# DM542T.net
KiCad netlist of a schematic drawn in EAGLE
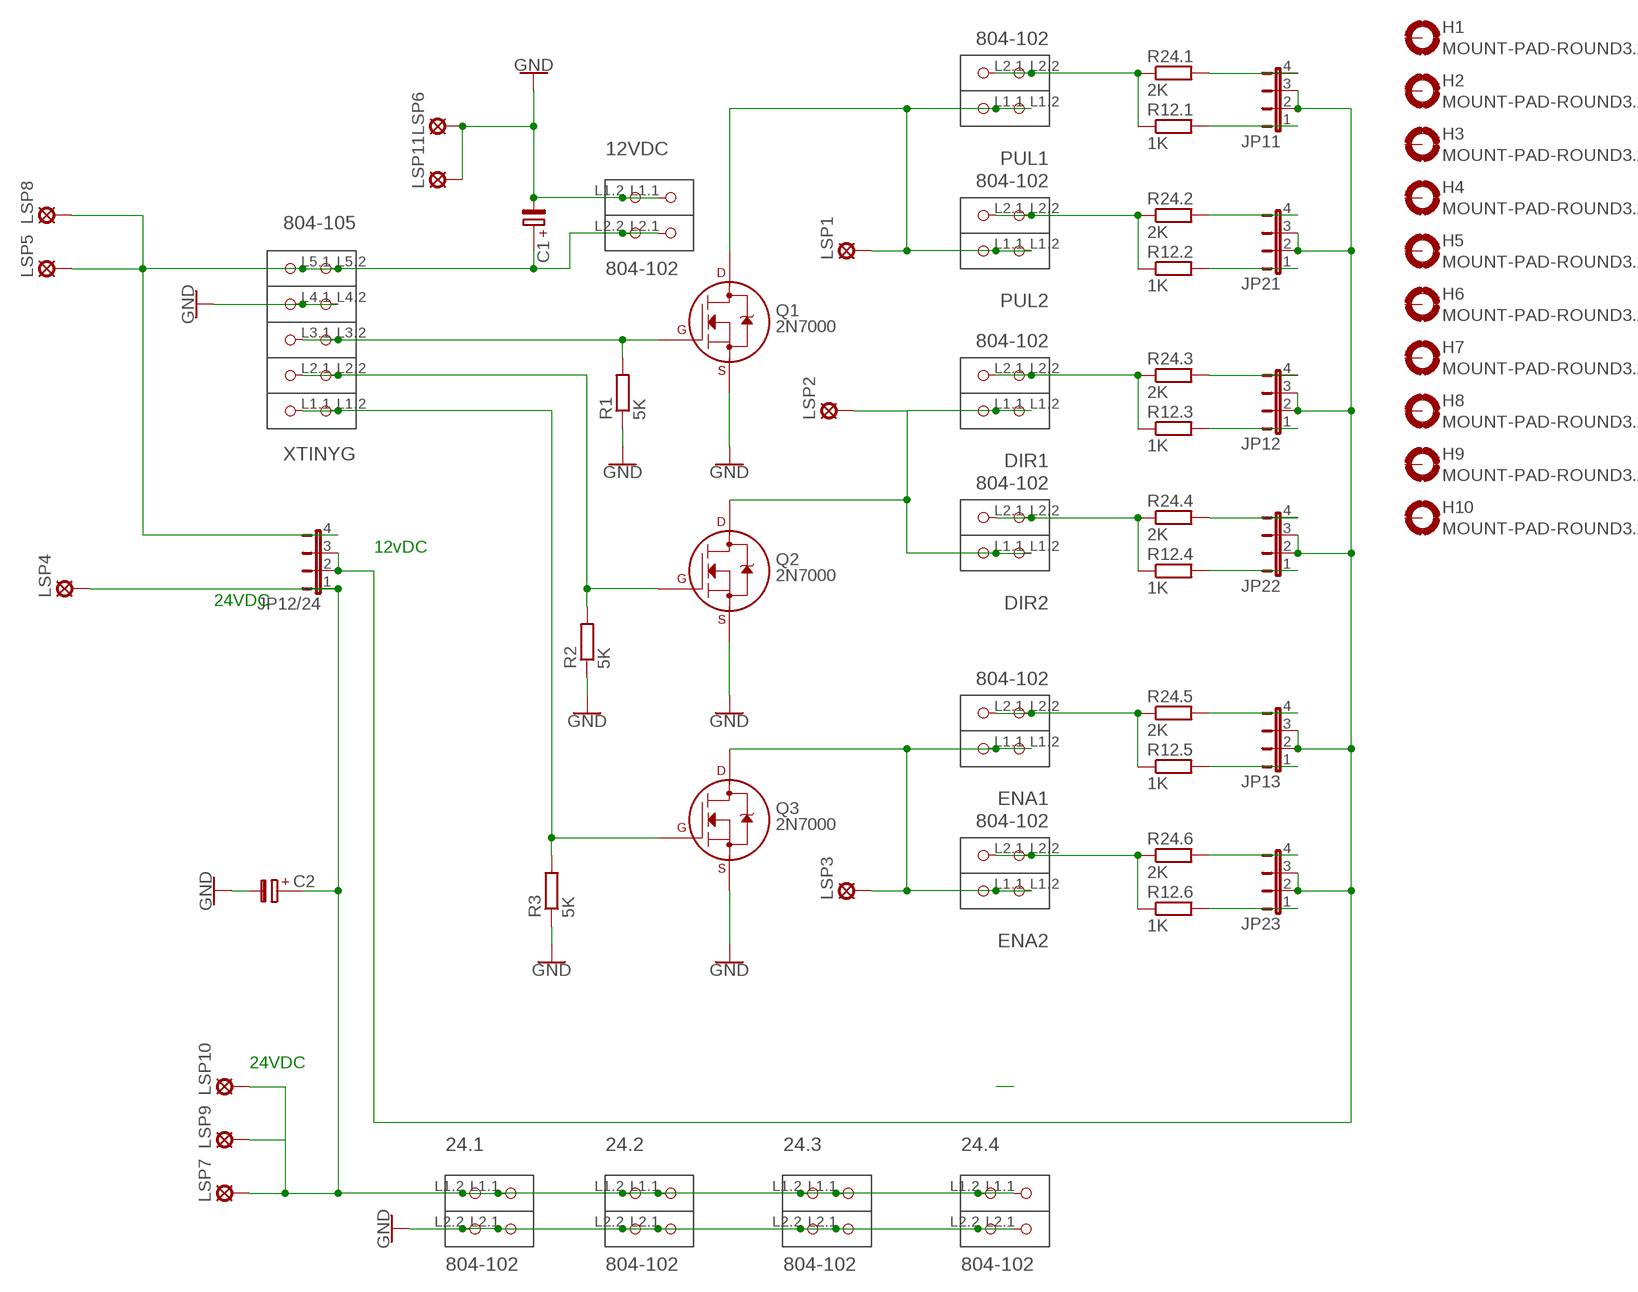
[diagram p0: schematic, sheet 1]

(export (version "E")
  (design (tool "Eeschema 10.0.6"))
  (components
    (comp (ref "12VDC")
      (value "804-102")
      (footprint "eagle-import:P-804-102")
      (libsource (lib "eagle-import") (part "804-102"))
    )
    (comp (ref "24.1")
      (value "804-102")
      (footprint "eagle-import:P-804-102")
      (libsource (lib "eagle-import") (part "804-102"))
    )
    (comp (ref "24.2")
      (value "804-102")
      (footprint "eagle-import:P-804-102")
      (libsource (lib "eagle-import") (part "804-102"))
    )
    (comp (ref "24.3")
      (value "804-102")
      (footprint "eagle-import:P-804-102")
      (libsource (lib "eagle-import") (part "804-102"))
    )
    (comp (ref "24.4")
      (value "804-102")
      (footprint "eagle-import:P-804-102")
      (libsource (lib "eagle-import") (part "804-102"))
    )
    (comp (ref "C1")
      (value "C-PR-3,5X10")
      (footprint "eagle-import:E3,5-10")
      (libsource (lib "eagle-import") (part "C-PR-3,5X10"))
    )
    (comp (ref "C2")
      (value "C-PR-3,5X10")
      (footprint "eagle-import:E3,5-10")
      (libsource (lib "eagle-import") (part "C-PR-3,5X10"))
    )
    (comp (ref "DIR1")
      (value "804-102")
      (footprint "eagle-import:P-804-102")
      (libsource (lib "eagle-import") (part "804-102"))
    )
    (comp (ref "DIR2")
      (value "804-102")
      (footprint "eagle-import:P-804-102")
      (libsource (lib "eagle-import") (part "804-102"))
    )
    (comp (ref "ENA1")
      (value "804-102")
      (footprint "eagle-import:P-804-102")
      (libsource (lib "eagle-import") (part "804-102"))
    )
    (comp (ref "ENA2")
      (value "804-102")
      (footprint "eagle-import:P-804-102")
      (libsource (lib "eagle-import") (part "804-102"))
    )
    (comp (ref "H1")
      (value "MOUNT-PAD-ROUND3.2")
      (footprint "eagle-import:3,2-PAD")
      (libsource (lib "eagle-import") (part "MOUNT-PAD-ROUND3.2"))
    )
    (comp (ref "H2")
      (value "MOUNT-PAD-ROUND3.2")
      (footprint "eagle-import:3,2-PAD")
      (libsource (lib "eagle-import") (part "MOUNT-PAD-ROUND3.2"))
    )
    (comp (ref "H3")
      (value "MOUNT-PAD-ROUND3.2")
      (footprint "eagle-import:3,2-PAD")
      (libsource (lib "eagle-import") (part "MOUNT-PAD-ROUND3.2"))
    )
    (comp (ref "H4")
      (value "MOUNT-PAD-ROUND3.2")
      (footprint "eagle-import:3,2-PAD")
      (libsource (lib "eagle-import") (part "MOUNT-PAD-ROUND3.2"))
    )
    (comp (ref "H5")
      (value "MOUNT-PAD-ROUND3.2")
      (footprint "eagle-import:3,2-PAD")
      (libsource (lib "eagle-import") (part "MOUNT-PAD-ROUND3.2"))
    )
    (comp (ref "H6")
      (value "MOUNT-PAD-ROUND3.2")
      (footprint "eagle-import:3,2-PAD")
      (libsource (lib "eagle-import") (part "MOUNT-PAD-ROUND3.2"))
    )
    (comp (ref "H7")
      (value "MOUNT-PAD-ROUND3.2")
      (footprint "eagle-import:3,2-PAD")
      (libsource (lib "eagle-import") (part "MOUNT-PAD-ROUND3.2"))
    )
    (comp (ref "H8")
      (value "MOUNT-PAD-ROUND3.2")
      (footprint "eagle-import:3,2-PAD")
      (libsource (lib "eagle-import") (part "MOUNT-PAD-ROUND3.2"))
    )
    (comp (ref "H9")
      (value "MOUNT-PAD-ROUND3.2")
      (footprint "eagle-import:3,2-PAD")
      (libsource (lib "eagle-import") (part "MOUNT-PAD-ROUND3.2"))
    )
    (comp (ref "H10")
      (value "MOUNT-PAD-ROUND3.2")
      (footprint "eagle-import:3,2-PAD")
      (libsource (lib "eagle-import") (part "MOUNT-PAD-ROUND3.2"))
    )
    (comp (ref "JP11")
      (value "JP4E")
      (footprint "eagle-import:JP4")
      (libsource (lib "eagle-import") (part "JP4E"))
    )
    (comp (ref "JP12")
      (value "JP4E")
      (footprint "eagle-import:JP4")
      (libsource (lib "eagle-import") (part "JP4E"))
    )
    (comp (ref "JP12/24")
      (value "JP4E")
      (footprint "eagle-import:JP4")
      (libsource (lib "eagle-import") (part "JP4E"))
    )
    (comp (ref "JP13")
      (value "JP4E")
      (footprint "eagle-import:JP4")
      (libsource (lib "eagle-import") (part "JP4E"))
    )
    (comp (ref "JP21")
      (value "JP4E")
      (footprint "eagle-import:JP4")
      (libsource (lib "eagle-import") (part "JP4E"))
    )
    (comp (ref "JP22")
      (value "JP4E")
      (footprint "eagle-import:JP4")
      (libsource (lib "eagle-import") (part "JP4E"))
    )
    (comp (ref "JP23")
      (value "JP4E")
      (footprint "eagle-import:JP4")
      (libsource (lib "eagle-import") (part "JP4E"))
    )
    (comp (ref "LSP1")
      (value "LSP10")
      (footprint "eagle-import:LSP10")
      (libsource (lib "eagle-import") (part "LSP10"))
    )
    (comp (ref "LSP2")
      (value "LSP10")
      (footprint "eagle-import:LSP10")
      (libsource (lib "eagle-import") (part "LSP10"))
    )
    (comp (ref "LSP3")
      (value "LSP10")
      (footprint "eagle-import:LSP10")
      (libsource (lib "eagle-import") (part "LSP10"))
    )
    (comp (ref "LSP4")
      (value "LSP10")
      (footprint "eagle-import:LSP10")
      (libsource (lib "eagle-import") (part "LSP10"))
    )
    (comp (ref "LSP5")
      (value "LSP10")
      (footprint "eagle-import:LSP10")
      (libsource (lib "eagle-import") (part "LSP10"))
    )
    (comp (ref "LSP6")
      (value "LSP10")
      (footprint "eagle-import:LSP10")
      (libsource (lib "eagle-import") (part "LSP10"))
    )
    (comp (ref "LSP7")
      (value "LSP10")
      (footprint "eagle-import:LSP10")
      (libsource (lib "eagle-import") (part "LSP10"))
    )
    (comp (ref "LSP8")
      (value "LSP10")
      (footprint "eagle-import:LSP10")
      (libsource (lib "eagle-import") (part "LSP10"))
    )
    (comp (ref "LSP9")
      (value "LSP10")
      (footprint "eagle-import:LSP10")
      (libsource (lib "eagle-import") (part "LSP10"))
    )
    (comp (ref "LSP10")
      (value "LSP10")
      (footprint "eagle-import:LSP10")
      (libsource (lib "eagle-import") (part "LSP10"))
    )
    (comp (ref "LSP11")
      (value "LSP10")
      (footprint "eagle-import:LSP10")
      (libsource (lib "eagle-import") (part "LSP10"))
    )
    (comp (ref "PUL1")
      (value "804-102")
      (footprint "eagle-import:P-804-102")
      (libsource (lib "eagle-import") (part "804-102"))
    )
    (comp (ref "PUL2")
      (value "804-102")
      (footprint "eagle-import:P-804-102")
      (libsource (lib "eagle-import") (part "804-102"))
    )
    (comp (ref "Q1")
      (value "2N7000")
      (footprint "eagle-import:TO-92")
      (libsource (lib "eagle-import") (part "2N700_TO920"))
    )
    (comp (ref "Q2")
      (value "2N7000")
      (footprint "eagle-import:TO-92")
      (libsource (lib "eagle-import") (part "2N700_TO920"))
    )
    (comp (ref "Q3")
      (value "2N7000")
      (footprint "eagle-import:TO-92")
      (libsource (lib "eagle-import") (part "2N700_TO920"))
    )
    (comp (ref "R1")
      (value "5K")
      (footprint "eagle-import:0207_15")
      (libsource (lib "eagle-import") (part "R-EU_0207/15"))
    )
    (comp (ref "R2")
      (value "5K")
      (footprint "eagle-import:0207_15")
      (libsource (lib "eagle-import") (part "R-EU_0207/15"))
    )
    (comp (ref "R3")
      (value "5K")
      (footprint "eagle-import:0207_15")
      (libsource (lib "eagle-import") (part "R-EU_0207/15"))
    )
    (comp (ref "R12.1")
      (value "1K")
      (footprint "eagle-import:0207_15")
      (libsource (lib "eagle-import") (part "R-EU_0207/15"))
    )
    (comp (ref "R12.2")
      (value "1K")
      (footprint "eagle-import:0207_15")
      (libsource (lib "eagle-import") (part "R-EU_0207/15"))
    )
    (comp (ref "R12.3")
      (value "1K")
      (footprint "eagle-import:0207_15")
      (libsource (lib "eagle-import") (part "R-EU_0207/15"))
    )
    (comp (ref "R12.4")
      (value "1K")
      (footprint "eagle-import:0207_15")
      (libsource (lib "eagle-import") (part "R-EU_0207/15"))
    )
    (comp (ref "R12.5")
      (value "1K")
      (footprint "eagle-import:0207_15")
      (libsource (lib "eagle-import") (part "R-EU_0207/15"))
    )
    (comp (ref "R12.6")
      (value "1K")
      (footprint "eagle-import:0207_15")
      (libsource (lib "eagle-import") (part "R-EU_0207/15"))
    )
    (comp (ref "R24.1")
      (value "2K")
      (footprint "eagle-import:0207_15")
      (libsource (lib "eagle-import") (part "R-EU_0207/15"))
    )
    (comp (ref "R24.2")
      (value "2K")
      (footprint "eagle-import:0207_15")
      (libsource (lib "eagle-import") (part "R-EU_0207/15"))
    )
    (comp (ref "R24.3")
      (value "2K")
      (footprint "eagle-import:0207_15")
      (libsource (lib "eagle-import") (part "R-EU_0207/15"))
    )
    (comp (ref "R24.4")
      (value "2K")
      (footprint "eagle-import:0207_15")
      (libsource (lib "eagle-import") (part "R-EU_0207/15"))
    )
    (comp (ref "R24.5")
      (value "2K")
      (footprint "eagle-import:0207_15")
      (libsource (lib "eagle-import") (part "R-EU_0207/15"))
    )
    (comp (ref "R24.6")
      (value "2K")
      (footprint "eagle-import:0207_15")
      (libsource (lib "eagle-import") (part "R-EU_0207/15"))
    )
    (comp (ref "XTINYG")
      (value "804-105")
      (footprint "eagle-import:P-804-105")
      (libsource (lib "eagle-import") (part "804-105"))
    )
  )
  (nets
    (net (code "1") (name "GND") (class "Default")
      (node (ref "12VDC") (pin "L1.1") (pinfunction "P1.1_L1.1") (pintype "bidirectional"))
      (node (ref "12VDC") (pin "L1.2") (pinfunction "P1.2_L1.2") (pintype "bidirectional"))
      (node (ref "24.1") (pin "L2.1") (pinfunction "P2.1_L2.1") (pintype "bidirectional"))
      (node (ref "24.1") (pin "L2.2") (pinfunction "P2.2_L2.2") (pintype "bidirectional"))
      (node (ref "24.2") (pin "L2.1") (pinfunction "P2.1_L2.1") (pintype "bidirectional"))
      (node (ref "24.2") (pin "L2.2") (pinfunction "P2.2_L2.2") (pintype "bidirectional"))
      (node (ref "24.3") (pin "L2.1") (pinfunction "P2.1_L2.1") (pintype "bidirectional"))
      (node (ref "24.3") (pin "L2.2") (pinfunction "P2.2_L2.2") (pintype "bidirectional"))
      (node (ref "24.4") (pin "L2.1") (pinfunction "P2.1_L2.1") (pintype "bidirectional"))
      (node (ref "24.4") (pin "L2.2") (pinfunction "P2.2_L2.2") (pintype "bidirectional"))
      (node (ref "C1") (pin "-") (pinfunction "-_-") (pintype "passive"))
      (node (ref "C2") (pin "-") (pinfunction "-_-") (pintype "passive"))
      (node (ref "LSP11") (pin "MP") (pinfunction "MP_MP") (pintype "passive"))
      (node (ref "LSP6") (pin "MP") (pinfunction "MP_MP") (pintype "passive"))
      (node (ref "Q1") (pin "1") (pinfunction "S_1") (pintype "bidirectional"))
      (node (ref "Q2") (pin "1") (pinfunction "S_1") (pintype "bidirectional"))
      (node (ref "Q3") (pin "1") (pinfunction "S_1") (pintype "bidirectional"))
      (node (ref "R1") (pin "1") (pinfunction "1_1") (pintype "passive"))
      (node (ref "R2") (pin "1") (pinfunction "1_1") (pintype "passive"))
      (node (ref "R3") (pin "1") (pinfunction "1_1") (pintype "passive"))
      (node (ref "XTINYG") (pin "L4.1") (pinfunction "P4.1_L4.1") (pintype "bidirectional"))
      (node (ref "XTINYG") (pin "L4.2") (pinfunction "P4.2_L4.2") (pintype "bidirectional"))
    )
    (net (code "2") (name "Net-(12VDC-P2.1)") (class "Default")
      (node (ref "12VDC") (pin "L2.1") (pinfunction "P2.1_L2.1") (pintype "bidirectional"))
      (node (ref "12VDC") (pin "L2.2") (pinfunction "P2.2_L2.2") (pintype "bidirectional"))
      (node (ref "C1") (pin "+") (pinfunction "+_+") (pintype "passive"))
      (node (ref "JP12/24") (pin "4") (pinfunction "4_4") (pintype "passive"))
      (node (ref "LSP5") (pin "MP") (pinfunction "MP_MP") (pintype "passive"))
      (node (ref "LSP8") (pin "MP") (pinfunction "MP_MP") (pintype "passive"))
      (node (ref "XTINYG") (pin "L5.1") (pinfunction "P5.1_L5.1") (pintype "bidirectional"))
      (node (ref "XTINYG") (pin "L5.2") (pinfunction "P5.2_L5.2") (pintype "bidirectional"))
    )
    (net (code "3") (name "Net-(24.1-P1.1)") (class "Default")
      (node (ref "24.1") (pin "L1.1") (pinfunction "P1.1_L1.1") (pintype "bidirectional"))
      (node (ref "24.1") (pin "L1.2") (pinfunction "P1.2_L1.2") (pintype "bidirectional"))
      (node (ref "24.2") (pin "L1.1") (pinfunction "P1.1_L1.1") (pintype "bidirectional"))
      (node (ref "24.2") (pin "L1.2") (pinfunction "P1.2_L1.2") (pintype "bidirectional"))
      (node (ref "24.3") (pin "L1.1") (pinfunction "P1.1_L1.1") (pintype "bidirectional"))
      (node (ref "24.3") (pin "L1.2") (pinfunction "P1.2_L1.2") (pintype "bidirectional"))
      (node (ref "24.4") (pin "L1.1") (pinfunction "P1.1_L1.1") (pintype "bidirectional"))
      (node (ref "24.4") (pin "L1.2") (pinfunction "P1.2_L1.2") (pintype "bidirectional"))
      (node (ref "C2") (pin "+") (pinfunction "+_+") (pintype "passive"))
      (node (ref "JP12/24") (pin "1") (pinfunction "1_1") (pintype "passive"))
      (node (ref "LSP10") (pin "MP") (pinfunction "MP_MP") (pintype "passive"))
      (node (ref "LSP4") (pin "MP") (pinfunction "MP_MP") (pintype "passive"))
      (node (ref "LSP7") (pin "MP") (pinfunction "MP_MP") (pintype "passive"))
      (node (ref "LSP9") (pin "MP") (pinfunction "MP_MP") (pintype "passive"))
    )
    (net (code "4") (name "Net-(DIR1-P1.1)") (class "Default")
      (node (ref "DIR1") (pin "L1.1") (pinfunction "P1.1_L1.1") (pintype "bidirectional"))
      (node (ref "DIR1") (pin "L1.2") (pinfunction "P1.2_L1.2") (pintype "bidirectional"))
      (node (ref "DIR2") (pin "L1.1") (pinfunction "P1.1_L1.1") (pintype "bidirectional"))
      (node (ref "DIR2") (pin "L1.2") (pinfunction "P1.2_L1.2") (pintype "bidirectional"))
      (node (ref "LSP2") (pin "MP") (pinfunction "MP_MP") (pintype "passive"))
      (node (ref "Q2") (pin "3") (pinfunction "D_3") (pintype "bidirectional"))
    )
    (net (code "5") (name "Net-(DIR1-P2.1)") (class "Default")
      (node (ref "DIR1") (pin "L2.1") (pinfunction "P2.1_L2.1") (pintype "bidirectional"))
      (node (ref "DIR1") (pin "L2.2") (pinfunction "P2.2_L2.2") (pintype "bidirectional"))
      (node (ref "R12.3") (pin "1") (pinfunction "1_1") (pintype "passive"))
      (node (ref "R24.3") (pin "1") (pinfunction "1_1") (pintype "passive"))
    )
    (net (code "6") (name "Net-(DIR2-P2.1)") (class "Default")
      (node (ref "DIR2") (pin "L2.1") (pinfunction "P2.1_L2.1") (pintype "bidirectional"))
      (node (ref "DIR2") (pin "L2.2") (pinfunction "P2.2_L2.2") (pintype "bidirectional"))
      (node (ref "R12.4") (pin "1") (pinfunction "1_1") (pintype "passive"))
      (node (ref "R24.4") (pin "1") (pinfunction "1_1") (pintype "passive"))
    )
    (net (code "7") (name "Net-(ENA1-P1.1)") (class "Default")
      (node (ref "ENA1") (pin "L1.1") (pinfunction "P1.1_L1.1") (pintype "bidirectional"))
      (node (ref "ENA1") (pin "L1.2") (pinfunction "P1.2_L1.2") (pintype "bidirectional"))
      (node (ref "ENA2") (pin "L1.1") (pinfunction "P1.1_L1.1") (pintype "bidirectional"))
      (node (ref "ENA2") (pin "L1.2") (pinfunction "P1.2_L1.2") (pintype "bidirectional"))
      (node (ref "LSP3") (pin "MP") (pinfunction "MP_MP") (pintype "passive"))
      (node (ref "Q3") (pin "3") (pinfunction "D_3") (pintype "bidirectional"))
    )
    (net (code "8") (name "Net-(ENA1-P2.1)") (class "Default")
      (node (ref "ENA1") (pin "L2.1") (pinfunction "P2.1_L2.1") (pintype "bidirectional"))
      (node (ref "ENA1") (pin "L2.2") (pinfunction "P2.2_L2.2") (pintype "bidirectional"))
      (node (ref "R12.5") (pin "1") (pinfunction "1_1") (pintype "passive"))
      (node (ref "R24.5") (pin "1") (pinfunction "1_1") (pintype "passive"))
    )
    (net (code "9") (name "Net-(ENA2-P2.1)") (class "Default")
      (node (ref "ENA2") (pin "L2.1") (pinfunction "P2.1_L2.1") (pintype "bidirectional"))
      (node (ref "ENA2") (pin "L2.2") (pinfunction "P2.2_L2.2") (pintype "bidirectional"))
      (node (ref "R12.6") (pin "1") (pinfunction "1_1") (pintype "passive"))
      (node (ref "R24.6") (pin "1") (pinfunction "1_1") (pintype "passive"))
    )
    (net (code "10") (name "Net-(JP11-Pad1)") (class "Default")
      (node (ref "JP11") (pin "1") (pinfunction "1_1") (pintype "passive"))
      (node (ref "R12.1") (pin "2") (pinfunction "2_2") (pintype "passive"))
    )
    (net (code "11") (name "Net-(JP11-Pad2)") (class "Default")
      (node (ref "JP11") (pin "2") (pinfunction "2_2") (pintype "passive"))
      (node (ref "JP11") (pin "3") (pinfunction "3_3") (pintype "passive"))
      (node (ref "JP12") (pin "2") (pinfunction "2_2") (pintype "passive"))
      (node (ref "JP12") (pin "3") (pinfunction "3_3") (pintype "passive"))
      (node (ref "JP12/24") (pin "2") (pinfunction "2_2") (pintype "passive"))
      (node (ref "JP12/24") (pin "3") (pinfunction "3_3") (pintype "passive"))
      (node (ref "JP13") (pin "2") (pinfunction "2_2") (pintype "passive"))
      (node (ref "JP13") (pin "3") (pinfunction "3_3") (pintype "passive"))
      (node (ref "JP21") (pin "2") (pinfunction "2_2") (pintype "passive"))
      (node (ref "JP21") (pin "3") (pinfunction "3_3") (pintype "passive"))
      (node (ref "JP22") (pin "2") (pinfunction "2_2") (pintype "passive"))
      (node (ref "JP22") (pin "3") (pinfunction "3_3") (pintype "passive"))
      (node (ref "JP23") (pin "2") (pinfunction "2_2") (pintype "passive"))
      (node (ref "JP23") (pin "3") (pinfunction "3_3") (pintype "passive"))
    )
    (net (code "12") (name "Net-(JP11-Pad4)") (class "Default")
      (node (ref "JP11") (pin "4") (pinfunction "4_4") (pintype "passive"))
      (node (ref "R24.1") (pin "2") (pinfunction "2_2") (pintype "passive"))
    )
    (net (code "13") (name "Net-(JP12-Pad1)") (class "Default")
      (node (ref "JP12") (pin "1") (pinfunction "1_1") (pintype "passive"))
      (node (ref "R12.3") (pin "2") (pinfunction "2_2") (pintype "passive"))
    )
    (net (code "14") (name "Net-(JP12-Pad4)") (class "Default")
      (node (ref "JP12") (pin "4") (pinfunction "4_4") (pintype "passive"))
      (node (ref "R24.3") (pin "2") (pinfunction "2_2") (pintype "passive"))
    )
    (net (code "15") (name "Net-(JP13-Pad1)") (class "Default")
      (node (ref "JP13") (pin "1") (pinfunction "1_1") (pintype "passive"))
      (node (ref "R12.5") (pin "2") (pinfunction "2_2") (pintype "passive"))
    )
    (net (code "16") (name "Net-(JP13-Pad4)") (class "Default")
      (node (ref "JP13") (pin "4") (pinfunction "4_4") (pintype "passive"))
      (node (ref "R24.5") (pin "2") (pinfunction "2_2") (pintype "passive"))
    )
    (net (code "17") (name "Net-(JP21-Pad1)") (class "Default")
      (node (ref "JP21") (pin "1") (pinfunction "1_1") (pintype "passive"))
      (node (ref "R12.2") (pin "2") (pinfunction "2_2") (pintype "passive"))
    )
    (net (code "18") (name "Net-(JP21-Pad4)") (class "Default")
      (node (ref "JP21") (pin "4") (pinfunction "4_4") (pintype "passive"))
      (node (ref "R24.2") (pin "2") (pinfunction "2_2") (pintype "passive"))
    )
    (net (code "19") (name "Net-(JP22-Pad1)") (class "Default")
      (node (ref "JP22") (pin "1") (pinfunction "1_1") (pintype "passive"))
      (node (ref "R12.4") (pin "2") (pinfunction "2_2") (pintype "passive"))
    )
    (net (code "20") (name "Net-(JP22-Pad4)") (class "Default")
      (node (ref "JP22") (pin "4") (pinfunction "4_4") (pintype "passive"))
      (node (ref "R24.4") (pin "2") (pinfunction "2_2") (pintype "passive"))
    )
    (net (code "21") (name "Net-(JP23-Pad1)") (class "Default")
      (node (ref "JP23") (pin "1") (pinfunction "1_1") (pintype "passive"))
      (node (ref "R12.6") (pin "2") (pinfunction "2_2") (pintype "passive"))
    )
    (net (code "22") (name "Net-(JP23-Pad4)") (class "Default")
      (node (ref "JP23") (pin "4") (pinfunction "4_4") (pintype "passive"))
      (node (ref "R24.6") (pin "2") (pinfunction "2_2") (pintype "passive"))
    )
    (net (code "23") (name "Net-(PUL1-P1.1)") (class "Default")
      (node (ref "LSP1") (pin "MP") (pinfunction "MP_MP") (pintype "passive"))
      (node (ref "PUL1") (pin "L1.1") (pinfunction "P1.1_L1.1") (pintype "bidirectional"))
      (node (ref "PUL1") (pin "L1.2") (pinfunction "P1.2_L1.2") (pintype "bidirectional"))
      (node (ref "PUL2") (pin "L1.1") (pinfunction "P1.1_L1.1") (pintype "bidirectional"))
      (node (ref "PUL2") (pin "L1.2") (pinfunction "P1.2_L1.2") (pintype "bidirectional"))
      (node (ref "Q1") (pin "3") (pinfunction "D_3") (pintype "bidirectional"))
    )
    (net (code "24") (name "Net-(PUL1-P2.1)") (class "Default")
      (node (ref "PUL1") (pin "L2.1") (pinfunction "P2.1_L2.1") (pintype "bidirectional"))
      (node (ref "PUL1") (pin "L2.2") (pinfunction "P2.2_L2.2") (pintype "bidirectional"))
      (node (ref "R12.1") (pin "1") (pinfunction "1_1") (pintype "passive"))
      (node (ref "R24.1") (pin "1") (pinfunction "1_1") (pintype "passive"))
    )
    (net (code "25") (name "Net-(PUL2-P2.1)") (class "Default")
      (node (ref "PUL2") (pin "L2.1") (pinfunction "P2.1_L2.1") (pintype "bidirectional"))
      (node (ref "PUL2") (pin "L2.2") (pinfunction "P2.2_L2.2") (pintype "bidirectional"))
      (node (ref "R12.2") (pin "1") (pinfunction "1_1") (pintype "passive"))
      (node (ref "R24.2") (pin "1") (pinfunction "1_1") (pintype "passive"))
    )
    (net (code "26") (name "Net-(Q1-G)") (class "Default")
      (node (ref "Q1") (pin "2") (pinfunction "G_2") (pintype "tri_state"))
      (node (ref "R1") (pin "2") (pinfunction "2_2") (pintype "passive"))
      (node (ref "XTINYG") (pin "L3.1") (pinfunction "P3.1_L3.1") (pintype "bidirectional"))
      (node (ref "XTINYG") (pin "L3.2") (pinfunction "P3.2_L3.2") (pintype "bidirectional"))
    )
    (net (code "27") (name "Net-(Q2-G)") (class "Default")
      (node (ref "Q2") (pin "2") (pinfunction "G_2") (pintype "tri_state"))
      (node (ref "R2") (pin "2") (pinfunction "2_2") (pintype "passive"))
      (node (ref "XTINYG") (pin "L2.1") (pinfunction "P2.1_L2.1") (pintype "bidirectional"))
      (node (ref "XTINYG") (pin "L2.2") (pinfunction "P2.2_L2.2") (pintype "bidirectional"))
    )
    (net (code "28") (name "Net-(Q3-G)") (class "Default")
      (node (ref "Q3") (pin "2") (pinfunction "G_2") (pintype "tri_state"))
      (node (ref "R3") (pin "2") (pinfunction "2_2") (pintype "passive"))
      (node (ref "XTINYG") (pin "L1.1") (pinfunction "P1.1_L1.1") (pintype "bidirectional"))
      (node (ref "XTINYG") (pin "L1.2") (pinfunction "P1.2_L1.2") (pintype "bidirectional"))
    )
    (net (code "29") (name "unconnected-(H1-MOUNT-PadB3,2)") (class "Default")
      (node (ref "H1") (pin "B3,2") (pinfunction "MOUNT_B3,2") (pintype "passive"))
    )
    (net (code "30") (name "unconnected-(H2-MOUNT-PadB3,2)") (class "Default")
      (node (ref "H2") (pin "B3,2") (pinfunction "MOUNT_B3,2") (pintype "passive"))
    )
    (net (code "31") (name "unconnected-(H3-MOUNT-PadB3,2)") (class "Default")
      (node (ref "H3") (pin "B3,2") (pinfunction "MOUNT_B3,2") (pintype "passive"))
    )
    (net (code "32") (name "unconnected-(H4-MOUNT-PadB3,2)") (class "Default")
      (node (ref "H4") (pin "B3,2") (pinfunction "MOUNT_B3,2") (pintype "passive"))
    )
    (net (code "33") (name "unconnected-(H5-MOUNT-PadB3,2)") (class "Default")
      (node (ref "H5") (pin "B3,2") (pinfunction "MOUNT_B3,2") (pintype "passive"))
    )
    (net (code "34") (name "unconnected-(H6-MOUNT-PadB3,2)") (class "Default")
      (node (ref "H6") (pin "B3,2") (pinfunction "MOUNT_B3,2") (pintype "passive"))
    )
    (net (code "35") (name "unconnected-(H7-MOUNT-PadB3,2)") (class "Default")
      (node (ref "H7") (pin "B3,2") (pinfunction "MOUNT_B3,2") (pintype "passive"))
    )
    (net (code "36") (name "unconnected-(H8-MOUNT-PadB3,2)") (class "Default")
      (node (ref "H8") (pin "B3,2") (pinfunction "MOUNT_B3,2") (pintype "passive"))
    )
    (net (code "37") (name "unconnected-(H9-MOUNT-PadB3,2)") (class "Default")
      (node (ref "H9") (pin "B3,2") (pinfunction "MOUNT_B3,2") (pintype "passive"))
    )
    (net (code "38") (name "unconnected-(H10-MOUNT-PadB3,2)") (class "Default")
      (node (ref "H10") (pin "B3,2") (pinfunction "MOUNT_B3,2") (pintype "passive"))
    )
  )
)
